# Power_driver_power.net
KiCad netlist of a schematic drawn in Altium Designer
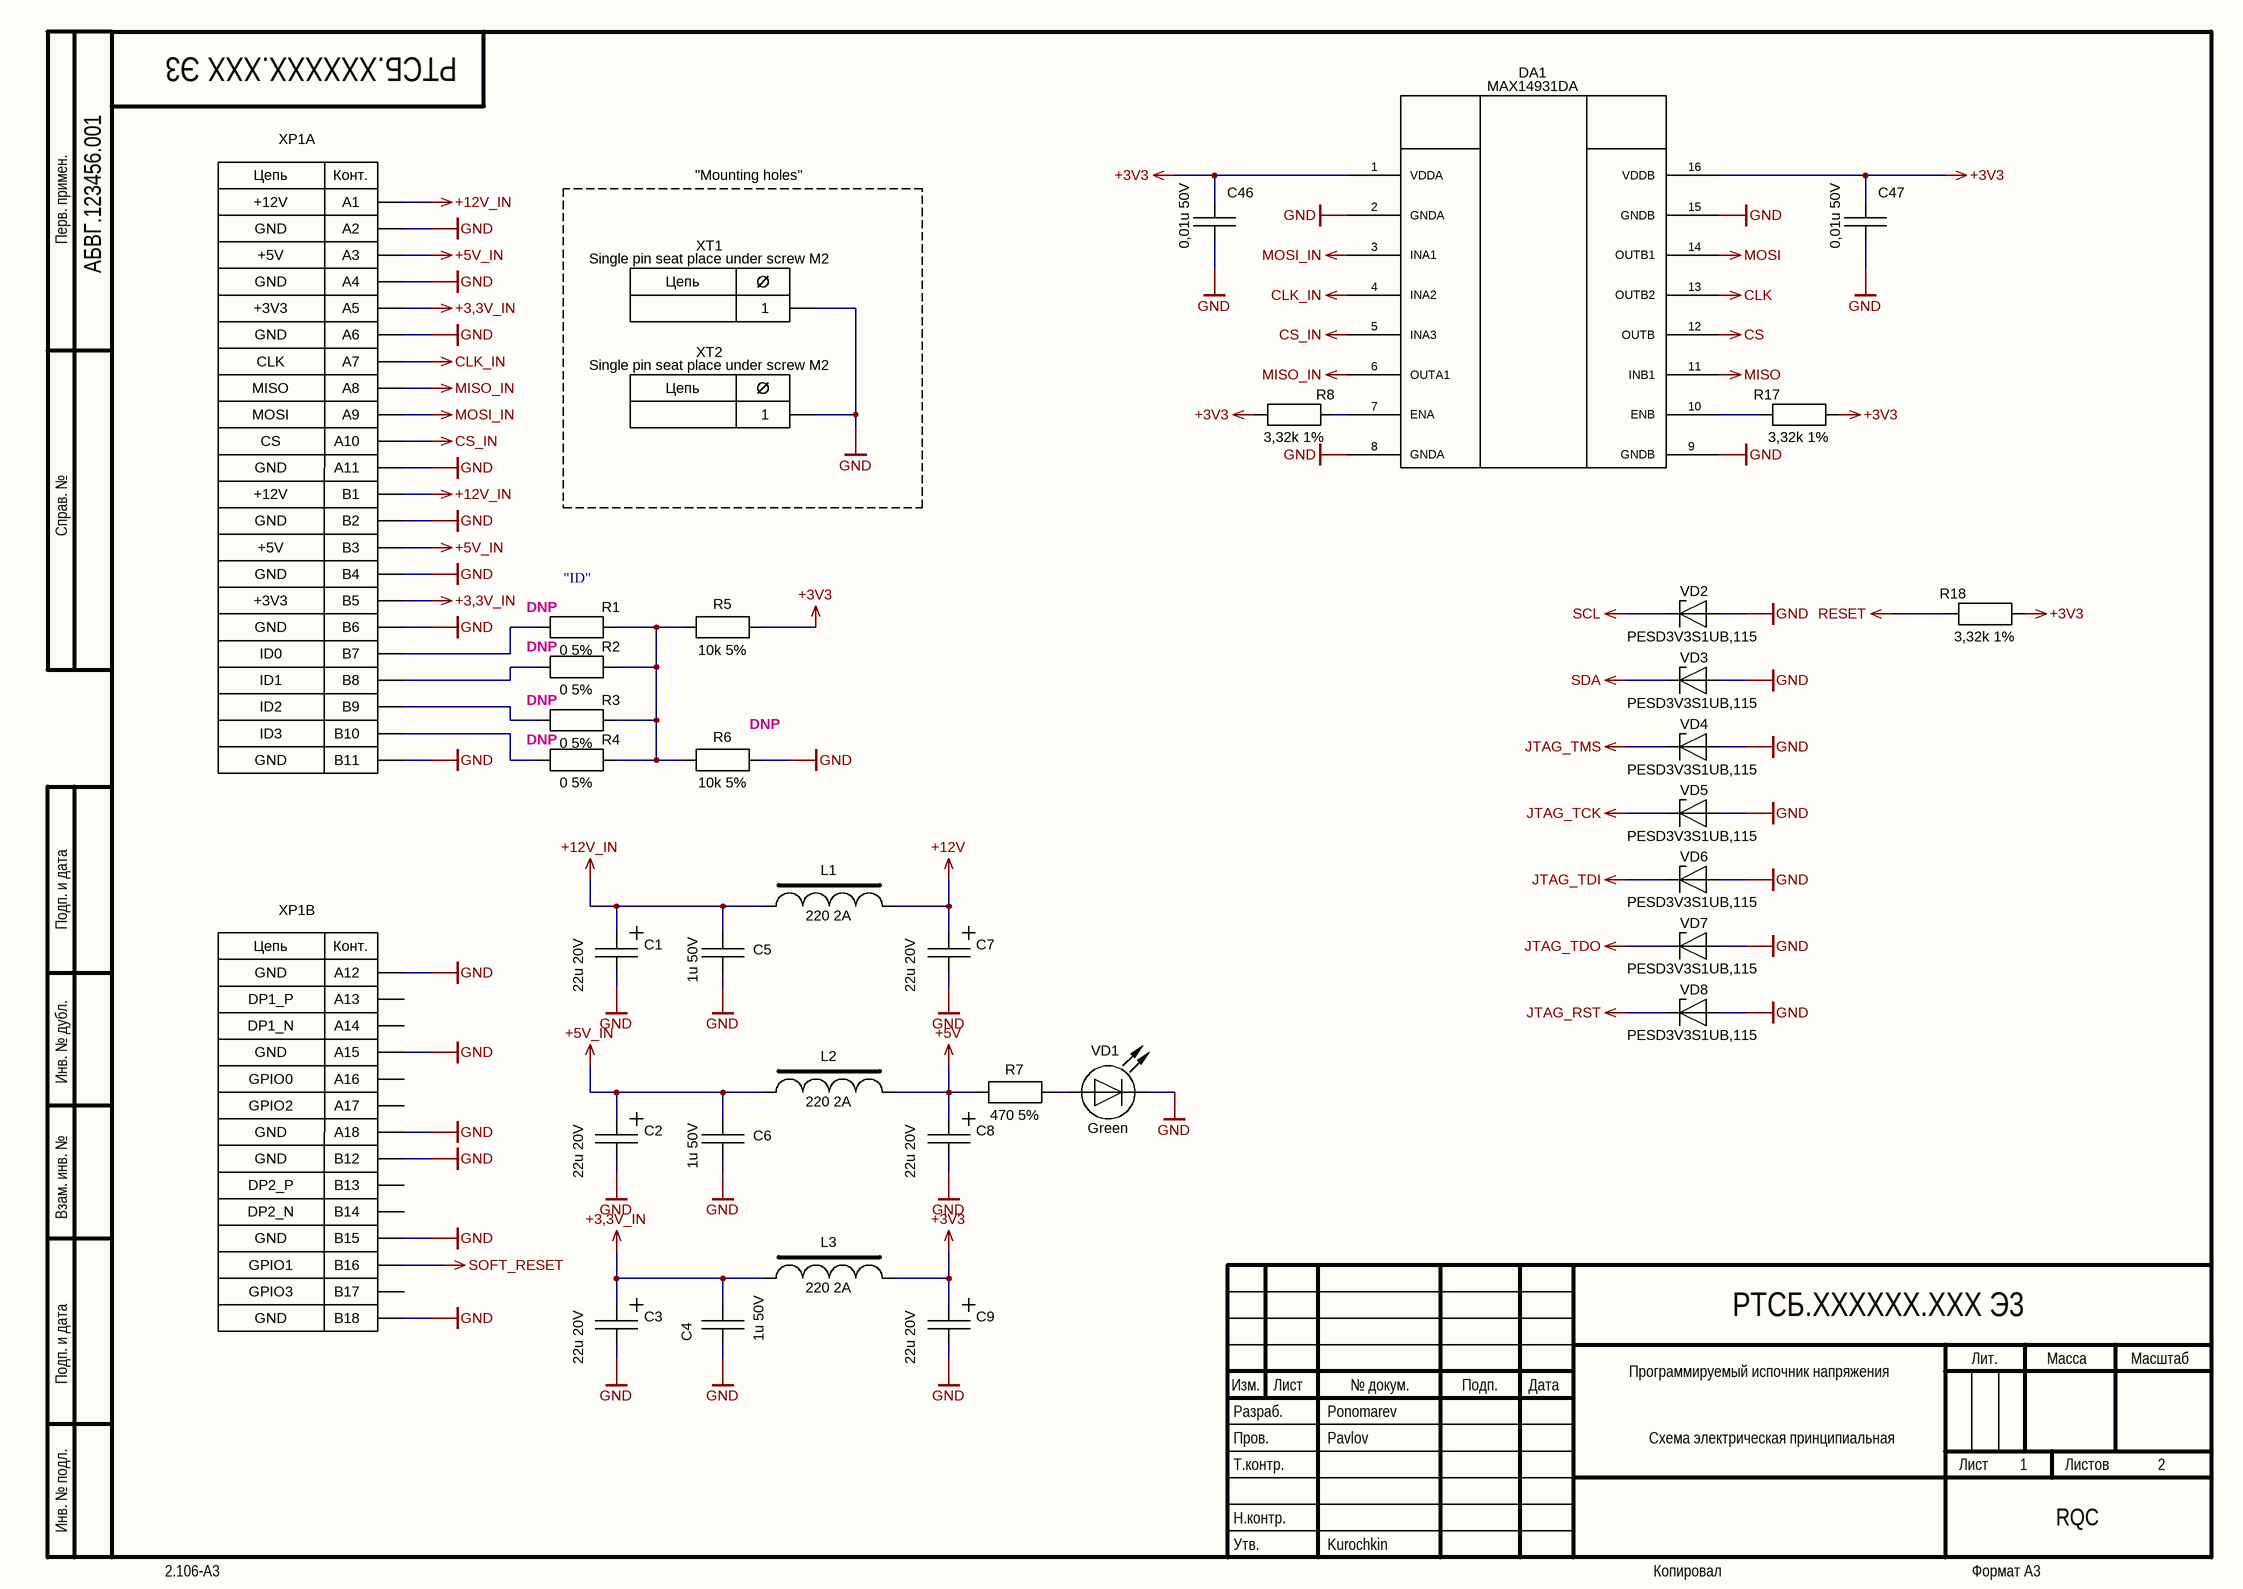
[diagram p0: Power_driver_power.SchDoc]

(export (version "E")
  (design (tool "Eeschema 10.0.6"))
  (components
    (comp (ref "C1")
      (value "22u 20V")
      (footprint "B_CAPMP3528X21N")
      (description "Solid Tantalum Capacitor, General purpose, Surface Mount")
      (fields
        (field (name "PARTNUMBER") "293D226X9020B2TE3")
        (field (name "MANUFACTURER") "Vishay")
        (field (name "DESIGNER") "Dudarev")
      )
      (libsource (lib "RQCLib") (part "Capacitor_Polar"))
    )
    (comp (ref "C2")
      (value "22u 20V")
      (footprint "B_CAPMP3528X21N")
      (description "Solid Tantalum Capacitor, General purpose, Surface Mount")
      (fields
        (field (name "PARTNUMBER") "293D226X9020B2TE3")
        (field (name "MANUFACTURER") "Vishay")
        (field (name "DESIGNER") "Dudarev")
      )
      (libsource (lib "RQCLib") (part "Capacitor_Polar"))
    )
    (comp (ref "C3")
      (value "22u 20V")
      (footprint "B_CAPMP3528X21N")
      (description "Solid Tantalum Capacitor, General purpose, Surface Mount")
      (fields
        (field (name "PARTNUMBER") "293D226X9020B2TE3")
        (field (name "MANUFACTURER") "Vishay")
        (field (name "DESIGNER") "Dudarev")
      )
      (libsource (lib "RQCLib") (part "Capacitor_Polar"))
    )
    (comp (ref "C4")
      (value "1u 50V")
      (footprint "C0603_CAPC1608X09N")
      (description "Конденсатор керамический (MLCC) общего назначения 0603")
      (fields
        (field (name "PARTNUMBER") "CC0603KRX7R9BB105")
        (field (name "MANUFACTURER") "YAGEO")
        (field (name "DESIGNER") "Dudarev")
      )
      (libsource (lib "RQCLib") (part "Capacitor"))
    )
    (comp (ref "C5")
      (value "1u 50V")
      (footprint "C0603_CAPC1608X09N")
      (description "Конденсатор керамический (MLCC) общего назначения 0603")
      (fields
        (field (name "PARTNUMBER") "CC0603KRX7R9BB105")
        (field (name "MANUFACTURER") "YAGEO")
        (field (name "DESIGNER") "Dudarev")
      )
      (libsource (lib "RQCLib") (part "Capacitor"))
    )
    (comp (ref "C6")
      (value "1u 50V")
      (footprint "C0603_CAPC1608X09N")
      (description "Конденсатор керамический (MLCC) общего назначения 0603")
      (fields
        (field (name "PARTNUMBER") "CC0603KRX7R9BB105")
        (field (name "MANUFACTURER") "YAGEO")
        (field (name "DESIGNER") "Dudarev")
      )
      (libsource (lib "RQCLib") (part "Capacitor"))
    )
    (comp (ref "C7")
      (value "22u 20V")
      (footprint "B_CAPMP3528X21N")
      (description "Solid Tantalum Capacitor, General purpose, Surface Mount")
      (fields
        (field (name "PARTNUMBER") "293D226X9020B2TE3")
        (field (name "MANUFACTURER") "Vishay")
        (field (name "DESIGNER") "Dudarev")
      )
      (libsource (lib "RQCLib") (part "Capacitor_Polar"))
    )
    (comp (ref "C8")
      (value "22u 20V")
      (footprint "B_CAPMP3528X21N")
      (description "Solid Tantalum Capacitor, General purpose, Surface Mount")
      (fields
        (field (name "PARTNUMBER") "293D226X9020B2TE3")
        (field (name "MANUFACTURER") "Vishay")
        (field (name "DESIGNER") "Dudarev")
      )
      (libsource (lib "RQCLib") (part "Capacitor_Polar"))
    )
    (comp (ref "C9")
      (value "22u 20V")
      (footprint "B_CAPMP3528X21N")
      (description "Solid Tantalum Capacitor, General purpose, Surface Mount")
      (fields
        (field (name "PARTNUMBER") "293D226X9020B2TE3")
        (field (name "MANUFACTURER") "Vishay")
        (field (name "DESIGNER") "Dudarev")
      )
      (libsource (lib "RQCLib") (part "Capacitor_Polar"))
    )
    (comp (ref "C46")
      (value "0,01u 50V")
      (footprint "C0603_CAPC1608X09N")
      (description "Конденсатор керамический (MLCC) общего назначения 0603")
      (fields
        (field (name "PARTNUMBER") "CC0603KRX7R9BB103")
        (field (name "MANUFACTURER") "YAGEO")
        (field (name "DESIGNER") "Dudarev")
      )
      (libsource (lib "RQCLib") (part "Capacitor"))
    )
    (comp (ref "C47")
      (value "0,01u 50V")
      (footprint "C0603_CAPC1608X09N")
      (description "Конденсатор керамический (MLCC) общего назначения 0603")
      (fields
        (field (name "PARTNUMBER") "CC0603KRX7R9BB103")
        (field (name "MANUFACTURER") "YAGEO")
        (field (name "DESIGNER") "Dudarev")
      )
      (libsource (lib "RQCLib") (part "Capacitor"))
    )
    (comp (ref "DA1")
      (value "MAX14931DA")
      (footprint "SOIC127P740X110-16N")
      (description "4-Channel, 1kVRMS, 2.75kVRMS,\r\n and 3.75kVRMS Digital Isolators")
      (libsource (lib "IC_ANALOG") (part "MAX14931DA"))
    )
    (comp (ref "L1")
      (value "220 2A")
      (footprint "I0805_INDC2012X11N")
      (description "Chip Ferrite Bead 220 Ohm, 2A, 0805")
      (fields
        (field (name "PARTNUMBER") "BLM21PG221SN1D")
        (field (name "MANUFACTURER") "Murata Electronics")
        (field (name "DESIGNER") "Pashinskiy")
      )
      (libsource (lib "RQCLib") (part "Inductor_Core"))
    )
    (comp (ref "L2")
      (value "220 2A")
      (footprint "I0805_INDC2012X11N")
      (description "Chip Ferrite Bead 220 Ohm, 2A, 0805")
      (fields
        (field (name "PARTNUMBER") "BLM21PG221SN1D")
        (field (name "MANUFACTURER") "Murata Electronics")
        (field (name "DESIGNER") "Pashinskiy")
      )
      (libsource (lib "RQCLib") (part "Inductor_Core"))
    )
    (comp (ref "L3")
      (value "220 2A")
      (footprint "I0805_INDC2012X11N")
      (description "Chip Ferrite Bead 220 Ohm, 2A, 0805")
      (fields
        (field (name "PARTNUMBER") "BLM21PG221SN1D")
        (field (name "MANUFACTURER") "Murata Electronics")
        (field (name "DESIGNER") "Pashinskiy")
      )
      (libsource (lib "RQCLib") (part "Inductor_Core"))
    )
    (comp (ref "R1")
      (value "0 5%")
      (footprint "R0603_RESC1608X06N")
      (description "Резистор толстопленочный общего назначения 0603")
      (fields
        (field (name "PARTNUMBER") "RC0603JR-070RL")
        (field (name "STAFF") "DNP")
        (field (name "MANUFACTURER") "YAGEO")
        (field (name "DESIGNER") "Dudarev")
      )
      (libsource (lib "RQCLib") (part "Resistor"))
    )
    (comp (ref "R2")
      (value "0 5%")
      (footprint "R0603_RESC1608X06N")
      (description "Резистор толстопленочный общего назначения 0603")
      (fields
        (field (name "PARTNUMBER") "RC0603JR-070RL")
        (field (name "STAFF") "DNP")
        (field (name "MANUFACTURER") "YAGEO")
        (field (name "DESIGNER") "Dudarev")
      )
      (libsource (lib "RQCLib") (part "Resistor"))
    )
    (comp (ref "R3")
      (value "0 5%")
      (footprint "R0603_RESC1608X06N")
      (description "Резистор толстопленочный общего назначения 0603")
      (fields
        (field (name "PARTNUMBER") "RC0603JR-070RL")
        (field (name "STAFF") "DNP")
        (field (name "MANUFACTURER") "YAGEO")
        (field (name "DESIGNER") "Dudarev")
      )
      (libsource (lib "RQCLib") (part "Resistor"))
    )
    (comp (ref "R4")
      (value "0 5%")
      (footprint "R0603_RESC1608X06N")
      (description "Резистор толстопленочный общего назначения 0603")
      (fields
        (field (name "PARTNUMBER") "RC0603JR-070RL")
        (field (name "STAFF") "DNP")
        (field (name "MANUFACTURER") "YAGEO")
        (field (name "DESIGNER") "Dudarev")
      )
      (libsource (lib "RQCLib") (part "Resistor"))
    )
    (comp (ref "R5")
      (value "10k 5%")
      (footprint "R0603_RESC1608X06N")
      (description "Резистор толстопленочный общего назначения 0603")
      (fields
        (field (name "PARTNUMBER") "RC0603JR-0710KL")
        (field (name "MANUFACTURER") "YAGEO")
        (field (name "DESIGNER") "Dudarev")
      )
      (libsource (lib "RQCLib") (part "Resistor"))
    )
    (comp (ref "R6")
      (value "10k 5%")
      (footprint "R0603_RESC1608X06N")
      (description "Резистор толстопленочный общего назначения 0603")
      (fields
        (field (name "PARTNUMBER") "RC0603JR-0710KL")
        (field (name "STAFF") "DNP")
        (field (name "MANUFACTURER") "YAGEO")
        (field (name "DESIGNER") "Dudarev")
      )
      (libsource (lib "RQCLib") (part "Resistor"))
    )
    (comp (ref "R7")
      (value "470 5%")
      (footprint "R0603_RESC1608X06N")
      (description "Резистор толстопленочный общего назначения 0603")
      (fields
        (field (name "PARTNUMBER") "RC0603JR-07470RL")
        (field (name "MANUFACTURER") "YAGEO")
        (field (name "DESIGNER") "Dudarev")
      )
      (libsource (lib "RQCLib") (part "Resistor"))
    )
    (comp (ref "R8")
      (value "3,32k 1%")
      (footprint "R0603_RESC1608X06N")
      (description "Резистор толстопленочный общего назначения 0603")
      (fields
        (field (name "PARTNUMBER") "RC0603FR-073K32L")
        (field (name "MANUFACTURER") "YAGEO")
        (field (name "DESIGNER") "Dudarev")
      )
      (libsource (lib "RQCLib") (part "Resistor"))
    )
    (comp (ref "R17")
      (value "3,32k 1%")
      (footprint "R0603_RESC1608X06N")
      (description "Резистор толстопленочный общего назначения 0603")
      (fields
        (field (name "PARTNUMBER") "RC0603FR-073K32L")
        (field (name "MANUFACTURER") "YAGEO")
        (field (name "DESIGNER") "Dudarev")
      )
      (libsource (lib "RQCLib") (part "Resistor"))
    )
    (comp (ref "R18")
      (value "3,32k 1%")
      (footprint "R0603_RESC1608X06N")
      (description "Резистор толстопленочный общего назначения 0603")
      (fields
        (field (name "PARTNUMBER") "RC0603FR-073K32L")
        (field (name "MANUFACTURER") "YAGEO")
        (field (name "DESIGNER") "Dudarev")
      )
      (libsource (lib "RQCLib") (part "Resistor"))
    )
    (comp (ref "VD1")
      (value "Green")
      (footprint "LED3010X012")
      (description "LED SMD Right Angle Bright Green 3mm x 1mm (1204)")
      (fields
        (field (name "PARTNUMBER") "155124VS73200")
        (field (name "MANUFACTURER") "Wurth Elektronik")
        (field (name "DESIGNER") "Dudarev")
      )
      (libsource (lib "RQCLib") (part "LED"))
    )
    (comp (ref "VD2")
      (value "PESD3V3S1UB,115")
      (footprint "SOD523_SODFL160X65-2N")
      (description "Transient Voltage Suppressor, 3.3V, Unidirectional,  SOD-523")
      (fields (field (name "MANUFACTURER") "NXP") (field (name "DESIGNER") "Pashinskiy"))
      (libsource (lib "RQCLib") (part "Diode_Zener"))
    )
    (comp (ref "VD3")
      (value "PESD3V3S1UB,115")
      (footprint "SOD523_SODFL160X65-2N")
      (description "Transient Voltage Suppressor, 3.3V, Unidirectional,  SOD-523")
      (fields (field (name "MANUFACTURER") "NXP") (field (name "DESIGNER") "Pashinskiy"))
      (libsource (lib "RQCLib") (part "Diode_Zener"))
    )
    (comp (ref "VD4")
      (value "PESD3V3S1UB,115")
      (footprint "SOD523_SODFL160X65-2N")
      (description "Transient Voltage Suppressor, 3.3V, Unidirectional,  SOD-523")
      (fields (field (name "MANUFACTURER") "NXP") (field (name "DESIGNER") "Pashinskiy"))
      (libsource (lib "RQCLib") (part "Diode_Zener"))
    )
    (comp (ref "VD5")
      (value "PESD3V3S1UB,115")
      (footprint "SOD523_SODFL160X65-2N")
      (description "Transient Voltage Suppressor, 3.3V, Unidirectional,  SOD-523")
      (fields (field (name "MANUFACTURER") "NXP") (field (name "DESIGNER") "Pashinskiy"))
      (libsource (lib "RQCLib") (part "Diode_Zener"))
    )
    (comp (ref "VD6")
      (value "PESD3V3S1UB,115")
      (footprint "SOD523_SODFL160X65-2N")
      (description "Transient Voltage Suppressor, 3.3V, Unidirectional,  SOD-523")
      (fields (field (name "MANUFACTURER") "NXP") (field (name "DESIGNER") "Pashinskiy"))
      (libsource (lib "RQCLib") (part "Diode_Zener"))
    )
    (comp (ref "VD7")
      (value "PESD3V3S1UB,115")
      (footprint "SOD523_SODFL160X65-2N")
      (description "Transient Voltage Suppressor, 3.3V, Unidirectional,  SOD-523")
      (fields (field (name "MANUFACTURER") "NXP") (field (name "DESIGNER") "Pashinskiy"))
      (libsource (lib "RQCLib") (part "Diode_Zener"))
    )
    (comp (ref "VD8")
      (value "PESD3V3S1UB,115")
      (footprint "SOD523_SODFL160X65-2N")
      (description "Transient Voltage Suppressor, 3.3V, Unidirectional,  SOD-523")
      (fields (field (name "MANUFACTURER") "NXP") (field (name "DESIGNER") "Pashinskiy"))
      (libsource (lib "RQCLib") (part "Diode_Zener"))
    )
    (comp (ref "XP1")
      (value "~")
      (footprint "PCI_EXP_36_EDGE_mod")
      (description "PCI Express connector 36 circuits")
      (libsource (lib "Connector_BUS") (part "PCI_EXP_36_EDGE_mod"))
    )
    (comp (ref "XT1")
      (value "Single pin seat place under screw M2")
      (footprint "S_MOUNT_M2")
      (fields
        (field (name "PARTNUMBER") "S_MOUNT_M2")
        (field (name "MANUFACTURER") "RQC")
        (field (name "DESIGNER") "Pashinskiy")
      )
      (libsource (lib "RQCLib") (part "X1_SCREW"))
    )
    (comp (ref "XT2")
      (value "Single pin seat place under screw M2")
      (footprint "S_MOUNT_M2")
      (fields
        (field (name "PARTNUMBER") "S_MOUNT_M2")
        (field (name "MANUFACTURER") "RQC")
        (field (name "DESIGNER") "Pashinskiy")
      )
      (libsource (lib "RQCLib") (part "X1_SCREW"))
    )
  )
  (nets
    (net (code "1") (name "+3,3V_IN") (class "Default")
      (node (ref "C3") (pin "1") (pinfunction "1_1") (pintype "passive"))
      (node (ref "C4") (pin "2") (pinfunction "2_2") (pintype "passive"))
      (node (ref "L3") (pin "1") (pinfunction "1_1") (pintype "passive"))
      (node (ref "XP1") (pin "A5") (pinfunction "A5_A5") (pintype "passive"))
      (node (ref "XP1") (pin "B5") (pinfunction "B5_B5") (pintype "passive"))
    )
    (net (code "2") (name "+3V3") (class "Default")
      (node (ref "C46") (pin "1") (pinfunction "1_1") (pintype "passive"))
      (node (ref "C47") (pin "1") (pinfunction "1_1") (pintype "passive"))
      (node (ref "C9") (pin "1") (pinfunction "1_1") (pintype "passive"))
      (node (ref "DA1") (pin "1") (pinfunction "VDDA_1") (pintype "passive"))
      (node (ref "DA1") (pin "16") (pinfunction "VDDB_16") (pintype "passive"))
      (node (ref "L3") (pin "2") (pinfunction "2_2") (pintype "passive"))
      (node (ref "R17") (pin "1") (pinfunction "1_1") (pintype "passive"))
      (node (ref "R18") (pin "1") (pinfunction "1_1") (pintype "passive"))
      (node (ref "R5") (pin "2") (pinfunction "2_2") (pintype "passive"))
      (node (ref "R8") (pin "1") (pinfunction "1_1") (pintype "passive"))
    )
    (net (code "3") (name "+5V") (class "Default")
      (node (ref "C8") (pin "1") (pinfunction "1_1") (pintype "passive"))
      (node (ref "L2") (pin "2") (pinfunction "2_2") (pintype "passive"))
      (node (ref "R7") (pin "1") (pinfunction "1_1") (pintype "passive"))
    )
    (net (code "4") (name "+5V_IN") (class "Default")
      (node (ref "C2") (pin "1") (pinfunction "1_1") (pintype "passive"))
      (node (ref "C6") (pin "2") (pinfunction "2_2") (pintype "passive"))
      (node (ref "L2") (pin "1") (pinfunction "1_1") (pintype "passive"))
      (node (ref "XP1") (pin "A3") (pinfunction "A3_A3") (pintype "passive"))
      (node (ref "XP1") (pin "B3") (pinfunction "B3_B3") (pintype "passive"))
    )
    (net (code "5") (name "+12V") (class "Default")
      (node (ref "C7") (pin "1") (pinfunction "1_1") (pintype "passive"))
      (node (ref "L1") (pin "2") (pinfunction "2_2") (pintype "passive"))
    )
    (net (code "6") (name "+12V_IN") (class "Default")
      (node (ref "C1") (pin "1") (pinfunction "1_1") (pintype "passive"))
      (node (ref "C5") (pin "2") (pinfunction "2_2") (pintype "passive"))
      (node (ref "L1") (pin "1") (pinfunction "1_1") (pintype "passive"))
      (node (ref "XP1") (pin "A1") (pinfunction "A1_A1") (pintype "passive"))
      (node (ref "XP1") (pin "B1") (pinfunction "B1_B1") (pintype "passive"))
    )
    (net (code "7") (name "CLK") (class "Default")
      (node (ref "DA1") (pin "13") (pinfunction "OUTB2_13") (pintype "passive"))
    )
    (net (code "8") (name "CLK_IN") (class "Default")
      (node (ref "DA1") (pin "4") (pinfunction "INA2_4") (pintype "passive"))
      (node (ref "XP1") (pin "A7") (pinfunction "A7_A7") (pintype "passive"))
    )
    (net (code "9") (name "CS") (class "Default")
      (node (ref "DA1") (pin "12") (pinfunction "OUTB_12") (pintype "passive"))
    )
    (net (code "10") (name "CS_IN") (class "Default")
      (node (ref "DA1") (pin "5") (pinfunction "INA3_5") (pintype "passive"))
      (node (ref "XP1") (pin "A10") (pinfunction "A10_A10") (pintype "passive"))
    )
    (net (code "11") (name "GND") (class "Default")
      (node (ref "C1") (pin "2") (pinfunction "2_2") (pintype "passive"))
      (node (ref "C2") (pin "2") (pinfunction "2_2") (pintype "passive"))
      (node (ref "C3") (pin "2") (pinfunction "2_2") (pintype "passive"))
      (node (ref "C4") (pin "1") (pinfunction "1_1") (pintype "passive"))
      (node (ref "C46") (pin "2") (pinfunction "2_2") (pintype "passive"))
      (node (ref "C47") (pin "2") (pinfunction "2_2") (pintype "passive"))
      (node (ref "C5") (pin "1") (pinfunction "1_1") (pintype "passive"))
      (node (ref "C6") (pin "1") (pinfunction "1_1") (pintype "passive"))
      (node (ref "C7") (pin "2") (pinfunction "2_2") (pintype "passive"))
      (node (ref "C8") (pin "2") (pinfunction "2_2") (pintype "passive"))
      (node (ref "C9") (pin "2") (pinfunction "2_2") (pintype "passive"))
      (node (ref "DA1") (pin "15") (pinfunction "GNDB_15") (pintype "passive"))
      (node (ref "DA1") (pin "2") (pinfunction "GNDA_2") (pintype "passive"))
      (node (ref "DA1") (pin "8") (pinfunction "GNDA_8") (pintype "passive"))
      (node (ref "DA1") (pin "9") (pinfunction "GNDB_9") (pintype "passive"))
      (node (ref "R6") (pin "2") (pinfunction "2_2") (pintype "passive"))
      (node (ref "VD1") (pin "1") (pinfunction "K_1") (pintype "passive"))
      (node (ref "VD2") (pin "2") (pinfunction "A_2") (pintype "passive"))
      (node (ref "VD3") (pin "2") (pinfunction "A_2") (pintype "passive"))
      (node (ref "VD4") (pin "2") (pinfunction "A_2") (pintype "passive"))
      (node (ref "VD5") (pin "2") (pinfunction "A_2") (pintype "passive"))
      (node (ref "VD6") (pin "2") (pinfunction "A_2") (pintype "passive"))
      (node (ref "VD7") (pin "2") (pinfunction "A_2") (pintype "passive"))
      (node (ref "VD8") (pin "2") (pinfunction "A_2") (pintype "passive"))
      (node (ref "XP1") (pin "A11") (pinfunction "A11_A11") (pintype "passive"))
      (node (ref "XP1") (pin "A12") (pinfunction "A12_A12") (pintype "passive"))
      (node (ref "XP1") (pin "A15") (pinfunction "A15_A15") (pintype "passive"))
      (node (ref "XP1") (pin "A18") (pinfunction "A18_A18") (pintype "passive"))
      (node (ref "XP1") (pin "A2") (pinfunction "A2_A2") (pintype "passive"))
      (node (ref "XP1") (pin "A4") (pinfunction "A4_A4") (pintype "passive"))
      (node (ref "XP1") (pin "A6") (pinfunction "A6_A6") (pintype "passive"))
      (node (ref "XP1") (pin "B11") (pinfunction "B11_B11") (pintype "passive"))
      (node (ref "XP1") (pin "B12") (pinfunction "B12_B12") (pintype "passive"))
      (node (ref "XP1") (pin "B15") (pinfunction "B15_B15") (pintype "passive"))
      (node (ref "XP1") (pin "B18") (pinfunction "B18_B18") (pintype "passive"))
      (node (ref "XP1") (pin "B2") (pinfunction "B2_B2") (pintype "passive"))
      (node (ref "XP1") (pin "B4") (pinfunction "B4_B4") (pintype "passive"))
      (node (ref "XP1") (pin "B6") (pinfunction "B6_B6") (pintype "passive"))
      (node (ref "XT1") (pin "1") (pinfunction "1_1") (pintype "passive"))
      (node (ref "XT2") (pin "1") (pinfunction "1_1") (pintype "passive"))
    )
    (net (code "12") (name "JTAG_RST") (class "Default")
      (node (ref "VD8") (pin "1") (pinfunction "K_1") (pintype "passive"))
    )
    (net (code "13") (name "JTAG_TCK") (class "Default")
      (node (ref "VD5") (pin "1") (pinfunction "K_1") (pintype "passive"))
    )
    (net (code "14") (name "JTAG_TDI") (class "Default")
      (node (ref "VD6") (pin "1") (pinfunction "K_1") (pintype "passive"))
    )
    (net (code "15") (name "JTAG_TDO") (class "Default")
      (node (ref "VD7") (pin "1") (pinfunction "K_1") (pintype "passive"))
    )
    (net (code "16") (name "JTAG_TMS") (class "Default")
      (node (ref "VD4") (pin "1") (pinfunction "K_1") (pintype "passive"))
    )
    (net (code "17") (name "MISO") (class "Default")
      (node (ref "DA1") (pin "11") (pinfunction "INB1_11") (pintype "passive"))
    )
    (net (code "18") (name "MISO_IN") (class "Default")
      (node (ref "DA1") (pin "6") (pinfunction "OUTA1_6") (pintype "passive"))
      (node (ref "XP1") (pin "A8") (pinfunction "A8_A8") (pintype "passive"))
    )
    (net (code "19") (name "MOSI") (class "Default")
      (node (ref "DA1") (pin "14") (pinfunction "OUTB1_14") (pintype "passive"))
    )
    (net (code "20") (name "MOSI_IN") (class "Default")
      (node (ref "DA1") (pin "3") (pinfunction "INA1_3") (pintype "passive"))
      (node (ref "XP1") (pin "A9") (pinfunction "A9_A9") (pintype "passive"))
    )
    (net (code "21") (name "Net-(DA1-ENA)") (class "Default")
      (node (ref "DA1") (pin "7") (pinfunction "ENA_7") (pintype "passive"))
      (node (ref "R8") (pin "2") (pinfunction "2_2") (pintype "passive"))
    )
    (net (code "22") (name "Net-(DA1-ENB)") (class "Default")
      (node (ref "DA1") (pin "10") (pinfunction "ENB_10") (pintype "passive"))
      (node (ref "R17") (pin "2") (pinfunction "2_2") (pintype "passive"))
    )
    (net (code "23") (name "Net-(R1-Pad1)") (class "Default")
      (node (ref "R1") (pin "1") (pinfunction "1_1") (pintype "passive"))
      (node (ref "XP1") (pin "B7") (pinfunction "B7_B7") (pintype "passive"))
    )
    (net (code "24") (name "Net-(R1-Pad2)") (class "Default")
      (node (ref "R1") (pin "2") (pinfunction "2_2") (pintype "passive"))
      (node (ref "R2") (pin "2") (pinfunction "2_2") (pintype "passive"))
      (node (ref "R3") (pin "2") (pinfunction "2_2") (pintype "passive"))
      (node (ref "R4") (pin "2") (pinfunction "2_2") (pintype "passive"))
      (node (ref "R5") (pin "1") (pinfunction "1_1") (pintype "passive"))
      (node (ref "R6") (pin "1") (pinfunction "1_1") (pintype "passive"))
    )
    (net (code "25") (name "Net-(R2-Pad1)") (class "Default")
      (node (ref "R2") (pin "1") (pinfunction "1_1") (pintype "passive"))
      (node (ref "XP1") (pin "B8") (pinfunction "B8_B8") (pintype "passive"))
    )
    (net (code "26") (name "Net-(R3-Pad1)") (class "Default")
      (node (ref "R3") (pin "1") (pinfunction "1_1") (pintype "passive"))
      (node (ref "XP1") (pin "B9") (pinfunction "B9_B9") (pintype "passive"))
    )
    (net (code "27") (name "Net-(R4-Pad1)") (class "Default")
      (node (ref "R4") (pin "1") (pinfunction "1_1") (pintype "passive"))
      (node (ref "XP1") (pin "B10") (pinfunction "B10_B10") (pintype "passive"))
    )
    (net (code "28") (name "Net-(VD1-A)") (class "Default")
      (node (ref "R7") (pin "2") (pinfunction "2_2") (pintype "passive"))
      (node (ref "VD1") (pin "2") (pinfunction "A_2") (pintype "passive"))
    )
    (net (code "29") (name "RESET") (class "Default")
      (node (ref "R18") (pin "2") (pinfunction "2_2") (pintype "passive"))
    )
    (net (code "30") (name "SCL") (class "Default")
      (node (ref "VD2") (pin "1") (pinfunction "K_1") (pintype "passive"))
    )
    (net (code "31") (name "SDA") (class "Default")
      (node (ref "VD3") (pin "1") (pinfunction "K_1") (pintype "passive"))
    )
    (net (code "32") (name "SOFT_RESET") (class "Default")
      (node (ref "XP1") (pin "B16") (pinfunction "B16_B16") (pintype "passive"))
    )
    (net (code "33") (name "unconnected-(XP1-PadA13)") (class "Default")
      (node (ref "XP1") (pin "A13") (pinfunction "A13_A13") (pintype "passive"))
    )
    (net (code "34") (name "unconnected-(XP1-PadA14)") (class "Default")
      (node (ref "XP1") (pin "A14") (pinfunction "A14_A14") (pintype "passive"))
    )
    (net (code "35") (name "unconnected-(XP1-PadA16)") (class "Default")
      (node (ref "XP1") (pin "A16") (pinfunction "A16_A16") (pintype "passive"))
    )
    (net (code "36") (name "unconnected-(XP1-PadA17)") (class "Default")
      (node (ref "XP1") (pin "A17") (pinfunction "A17_A17") (pintype "passive"))
    )
    (net (code "37") (name "unconnected-(XP1-PadB13)") (class "Default")
      (node (ref "XP1") (pin "B13") (pinfunction "B13_B13") (pintype "passive"))
    )
    (net (code "38") (name "unconnected-(XP1-PadB14)") (class "Default")
      (node (ref "XP1") (pin "B14") (pinfunction "B14_B14") (pintype "passive"))
    )
    (net (code "39") (name "unconnected-(XP1-PadB17)") (class "Default")
      (node (ref "XP1") (pin "B17") (pinfunction "B17_B17") (pintype "passive"))
    )
  )
)
